# evpr_mini.net
KiCad netlist of a schematic drawn in EAGLE
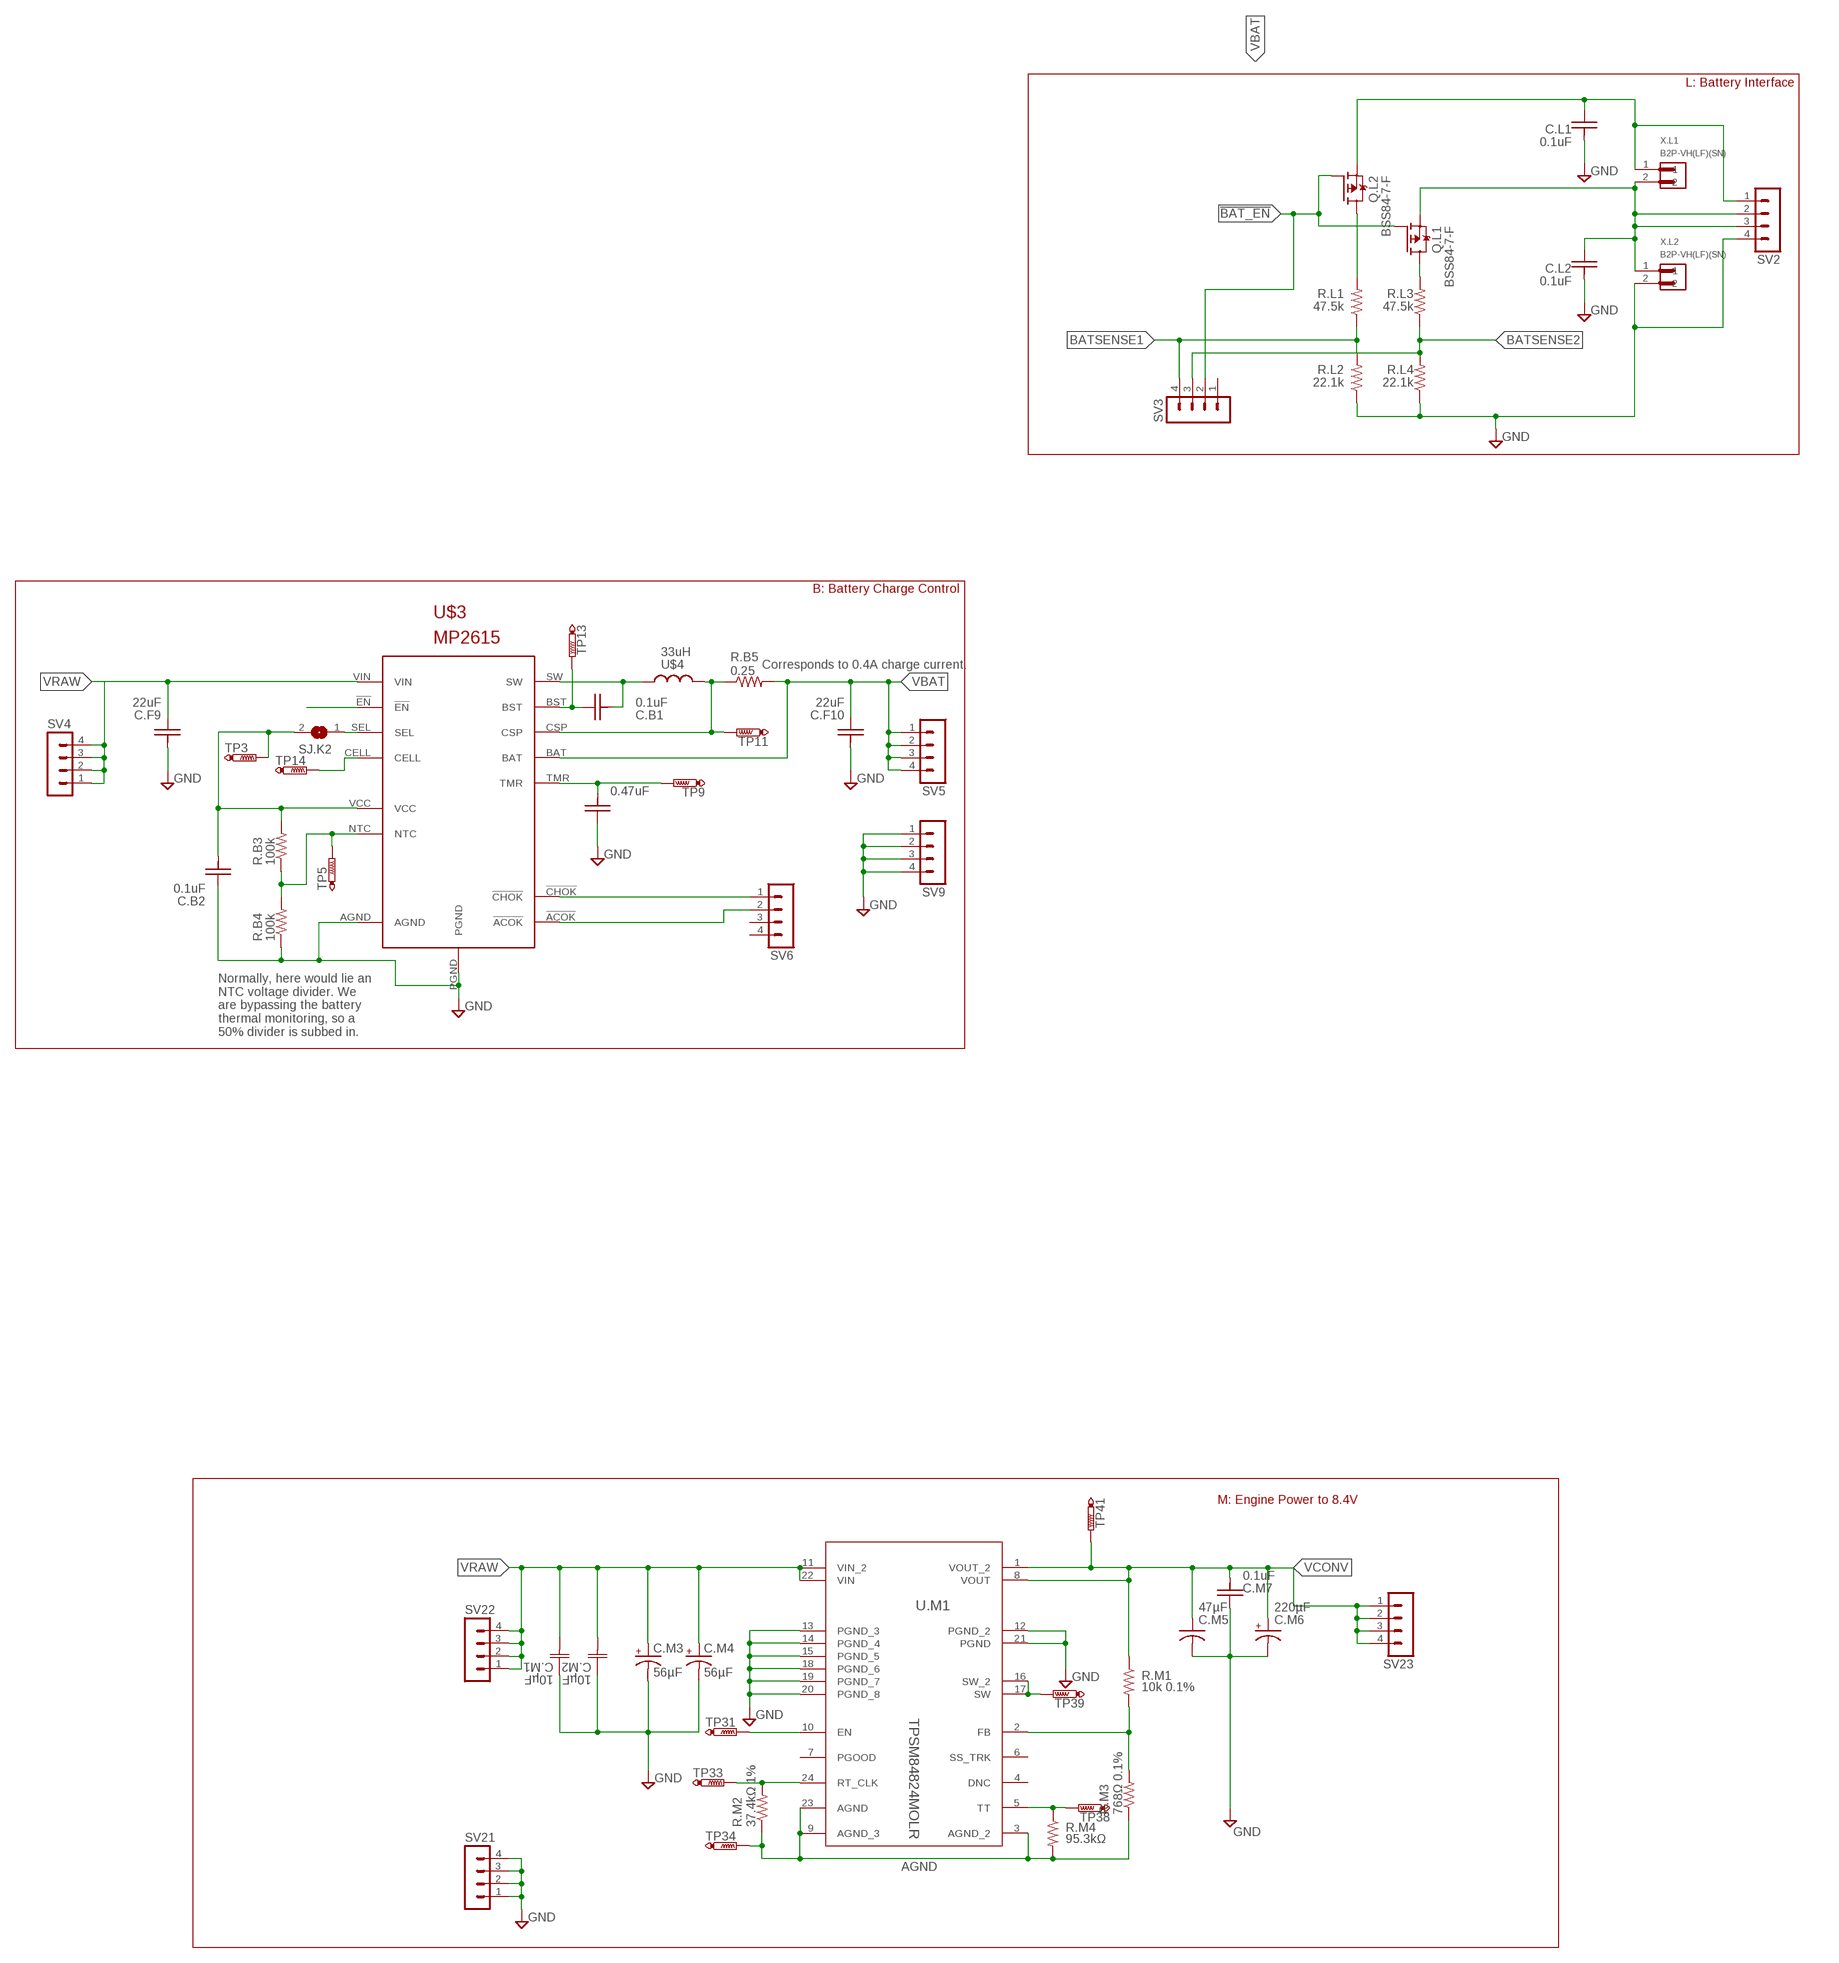
[diagram p0: schematic, sheet 1, part 1 of 2]
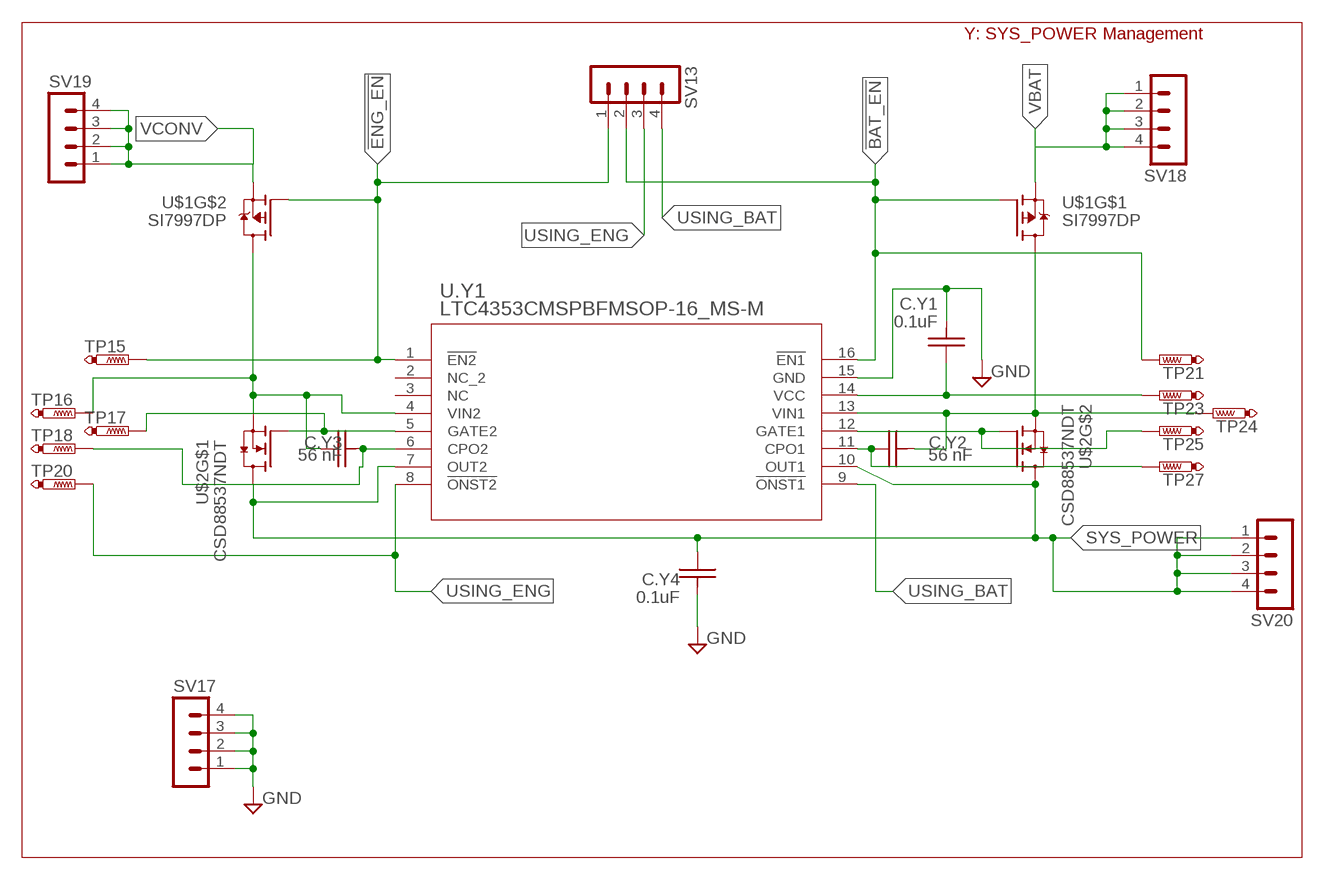
[diagram p1: schematic, sheet 1, part 2 of 2]

(export (version "E")
  (design (tool "Eeschema 10.0.6"))
  (components
    (comp (ref "C.B1")
      (value "0.1uF")
      (footprint "eagle-import:C0603")
      (libsource (lib "eagle-import") (part "C0603"))
    )
    (comp (ref "C.B2")
      (value "0.1uF")
      (footprint "eagle-import:C0603")
      (libsource (lib "eagle-import") (part "C0603"))
    )
    (comp (ref "C.F9")
      (value "22uF")
      (footprint "eagle-import:C0603")
      (libsource (lib "eagle-import") (part "C0603"))
    )
    (comp (ref "C.F10")
      (value "22uF")
      (footprint "eagle-import:C0603")
      (libsource (lib "eagle-import") (part "C0603"))
    )
    (comp (ref "C.J3")
      (value "0.47uF")
      (footprint "eagle-import:C0603")
      (libsource (lib "eagle-import") (part "C0603"))
    )
    (comp (ref "C.L1")
      (value "0.1uF")
      (footprint "eagle-import:C0603")
      (libsource (lib "eagle-import") (part "C0603"))
    )
    (comp (ref "C.L2")
      (value "0.1uF")
      (footprint "eagle-import:C0603")
      (libsource (lib "eagle-import") (part "C0603"))
    )
    (comp (ref "C.M1")
      (value "10µF")
      (footprint "eagle-import:CAP_3225")
      (libsource (lib "eagle-import") (part "C3225X7R1E106K250AC"))
    )
    (comp (ref "C.M2")
      (value "10µF")
      (footprint "eagle-import:CAP_3225")
      (libsource (lib "eagle-import") (part "C3225X7R1E106K250AC"))
    )
    (comp (ref "C.M3")
      (value "56µF")
      (footprint "eagle-import:OSCON_SVPF_6.3MM")
      (libsource (lib "eagle-import") (part "6.3MMCAP"))
    )
    (comp (ref "C.M4")
      (value "56µF")
      (footprint "eagle-import:OSCON_SVPF_6.3MM")
      (libsource (lib "eagle-import") (part "6.3MMCAP"))
    )
    (comp (ref "C.M5")
      (value "47µF")
      (footprint "eagle-import:C1210")
      (libsource (lib "eagle-import") (part "C-USC1210"))
    )
    (comp (ref "C.M6")
      (value "220µF")
      (footprint "eagle-import:C6CYLCAP")
      (libsource (lib "eagle-import") (part "WURTH875115352003"))
    )
    (comp (ref "C.M7")
      (value "0.1uF")
      (footprint "eagle-import:C0603")
      (libsource (lib "eagle-import") (part "C0603"))
    )
    (comp (ref "C.Y1")
      (value "0.1uF")
      (footprint "eagle-import:C0603")
      (libsource (lib "eagle-import") (part "C0603"))
    )
    (comp (ref "C.Y2")
      (value "56 nF")
      (footprint "eagle-import:C0603")
      (libsource (lib "eagle-import") (part "C0603"))
    )
    (comp (ref "C.Y3")
      (value "56 nF")
      (footprint "eagle-import:C0603")
      (libsource (lib "eagle-import") (part "C0603"))
    )
    (comp (ref "C.Y4")
      (value "0.1uF")
      (footprint "eagle-import:C0603")
      (libsource (lib "eagle-import") (part "C0603"))
    )
    (comp (ref "Q.L1")
      (value "BSS84-7-F")
      (footprint "eagle-import:SOT23")
      (libsource (lib "eagle-import") (part "BSS84-7-F"))
    )
    (comp (ref "Q.L2")
      (value "BSS84-7-F")
      (footprint "eagle-import:SOT23")
      (libsource (lib "eagle-import") (part "BSS84-7-F"))
    )
    (comp (ref "R.B3")
      (value "100k")
      (footprint "eagle-import:R0603")
      (libsource (lib "eagle-import") (part "R0603"))
    )
    (comp (ref "R.B4")
      (value "100k")
      (footprint "eagle-import:R0603")
      (libsource (lib "eagle-import") (part "R0603"))
    )
    (comp (ref "R.B5")
      (value "0.25")
      (footprint "eagle-import:R0603")
      (libsource (lib "eagle-import") (part "R0603"))
    )
    (comp (ref "R.L1")
      (value "47.5k")
      (footprint "eagle-import:R0603")
      (libsource (lib "eagle-import") (part "R0603"))
    )
    (comp (ref "R.L2")
      (value "22.1k")
      (footprint "eagle-import:R0603")
      (libsource (lib "eagle-import") (part "R0603"))
    )
    (comp (ref "R.L3")
      (value "47.5k")
      (footprint "eagle-import:R0603")
      (libsource (lib "eagle-import") (part "R0603"))
    )
    (comp (ref "R.L4")
      (value "22.1k")
      (footprint "eagle-import:R0603")
      (libsource (lib "eagle-import") (part "R0603"))
    )
    (comp (ref "R.M1")
      (value "10k 0.1%")
      (footprint "eagle-import:R0603")
      (libsource (lib "eagle-import") (part "R0603"))
    )
    (comp (ref "R.M2")
      (value "37.4kΩ 1%")
      (footprint "eagle-import:R0603")
      (libsource (lib "eagle-import") (part "R0603"))
    )
    (comp (ref "R.M3")
      (value "768Ω 0.1%")
      (footprint "eagle-import:R0603")
      (libsource (lib "eagle-import") (part "R0603"))
    )
    (comp (ref "R.M4")
      (value "95.3kΩ")
      (footprint "eagle-import:R0603")
      (libsource (lib "eagle-import") (part "R0603"))
    )
    (comp (ref "SJ.K2")
      (value "SJ")
      (footprint "eagle-import:SJ")
      (libsource (lib "eagle-import") (part "SJ"))
    )
    (comp (ref "SV2")
      (value "MA04-1")
      (footprint "eagle-import:MA04-1")
      (libsource (lib "eagle-import") (part "MA04-1"))
    )
    (comp (ref "SV3")
      (value "MA04-1")
      (footprint "eagle-import:MA04-1")
      (libsource (lib "eagle-import") (part "MA04-1"))
    )
    (comp (ref "SV4")
      (value "MA04-1")
      (footprint "eagle-import:MA04-1")
      (libsource (lib "eagle-import") (part "MA04-1"))
    )
    (comp (ref "SV5")
      (value "MA04-1")
      (footprint "eagle-import:MA04-1")
      (libsource (lib "eagle-import") (part "MA04-1"))
    )
    (comp (ref "SV6")
      (value "MA04-1")
      (footprint "eagle-import:MA04-1")
      (libsource (lib "eagle-import") (part "MA04-1"))
    )
    (comp (ref "SV9")
      (value "MA04-1")
      (footprint "eagle-import:MA04-1")
      (libsource (lib "eagle-import") (part "MA04-1"))
    )
    (comp (ref "SV13")
      (value "MA04-1")
      (footprint "eagle-import:MA04-1")
      (libsource (lib "eagle-import") (part "MA04-1"))
    )
    (comp (ref "SV17")
      (value "MA04-1")
      (footprint "eagle-import:MA04-1")
      (libsource (lib "eagle-import") (part "MA04-1"))
    )
    (comp (ref "SV18")
      (value "MA04-1")
      (footprint "eagle-import:MA04-1")
      (libsource (lib "eagle-import") (part "MA04-1"))
    )
    (comp (ref "SV19")
      (value "MA04-1")
      (footprint "eagle-import:MA04-1")
      (libsource (lib "eagle-import") (part "MA04-1"))
    )
    (comp (ref "SV20")
      (value "MA04-1")
      (footprint "eagle-import:MA04-1")
      (libsource (lib "eagle-import") (part "MA04-1"))
    )
    (comp (ref "SV21")
      (value "MA04-1")
      (footprint "eagle-import:MA04-1")
      (libsource (lib "eagle-import") (part "MA04-1"))
    )
    (comp (ref "SV22")
      (value "MA04-1")
      (footprint "eagle-import:MA04-1")
      (libsource (lib "eagle-import") (part "MA04-1"))
    )
    (comp (ref "SV23")
      (value "MA04-1")
      (footprint "eagle-import:MA04-1")
      (libsource (lib "eagle-import") (part "MA04-1"))
    )
    (comp (ref "TP3")
      (value "PTR1TP10R")
      (footprint "eagle-import:TP10R")
      (libsource (lib "eagle-import") (part "PTR1TP10R"))
    )
    (comp (ref "TP5")
      (value "PTR1TP10R")
      (footprint "eagle-import:TP10R")
      (libsource (lib "eagle-import") (part "PTR1TP10R"))
    )
    (comp (ref "TP9")
      (value "PTR1TP10R")
      (footprint "eagle-import:TP10R")
      (libsource (lib "eagle-import") (part "PTR1TP10R"))
    )
    (comp (ref "TP11")
      (value "PTR1TP10R")
      (footprint "eagle-import:TP10R")
      (libsource (lib "eagle-import") (part "PTR1TP10R"))
    )
    (comp (ref "TP13")
      (value "PTR1TP10R")
      (footprint "eagle-import:TP10R")
      (libsource (lib "eagle-import") (part "PTR1TP10R"))
    )
    (comp (ref "TP14")
      (value "PTR1TP10R")
      (footprint "eagle-import:TP10R")
      (libsource (lib "eagle-import") (part "PTR1TP10R"))
    )
    (comp (ref "TP15")
      (value "PTR1TP10R")
      (footprint "eagle-import:TP10R")
      (libsource (lib "eagle-import") (part "PTR1TP10R"))
    )
    (comp (ref "TP16")
      (value "PTR1TP10R")
      (footprint "eagle-import:TP10R")
      (libsource (lib "eagle-import") (part "PTR1TP10R"))
    )
    (comp (ref "TP17")
      (value "PTR1TP10R")
      (footprint "eagle-import:TP10R")
      (libsource (lib "eagle-import") (part "PTR1TP10R"))
    )
    (comp (ref "TP18")
      (value "PTR1TP10R")
      (footprint "eagle-import:TP10R")
      (libsource (lib "eagle-import") (part "PTR1TP10R"))
    )
    (comp (ref "TP20")
      (value "PTR1TP10R")
      (footprint "eagle-import:TP10R")
      (libsource (lib "eagle-import") (part "PTR1TP10R"))
    )
    (comp (ref "TP21")
      (value "PTR1TP10R")
      (footprint "eagle-import:TP10R")
      (libsource (lib "eagle-import") (part "PTR1TP10R"))
    )
    (comp (ref "TP23")
      (value "PTR1TP10R")
      (footprint "eagle-import:TP10R")
      (libsource (lib "eagle-import") (part "PTR1TP10R"))
    )
    (comp (ref "TP24")
      (value "PTR1TP10R")
      (footprint "eagle-import:TP10R")
      (libsource (lib "eagle-import") (part "PTR1TP10R"))
    )
    (comp (ref "TP25")
      (value "PTR1TP10R")
      (footprint "eagle-import:TP10R")
      (libsource (lib "eagle-import") (part "PTR1TP10R"))
    )
    (comp (ref "TP27")
      (value "PTR1TP10R")
      (footprint "eagle-import:TP10R")
      (libsource (lib "eagle-import") (part "PTR1TP10R"))
    )
    (comp (ref "TP31")
      (value "PTR1TP10R")
      (footprint "eagle-import:TP10R")
      (libsource (lib "eagle-import") (part "PTR1TP10R"))
    )
    (comp (ref "TP33")
      (value "PTR1TP10R")
      (footprint "eagle-import:TP10R")
      (libsource (lib "eagle-import") (part "PTR1TP10R"))
    )
    (comp (ref "TP34")
      (value "PTR1TP10R")
      (footprint "eagle-import:TP10R")
      (libsource (lib "eagle-import") (part "PTR1TP10R"))
    )
    (comp (ref "TP38")
      (value "PTR1TP10R")
      (footprint "eagle-import:TP10R")
      (libsource (lib "eagle-import") (part "PTR1TP10R"))
    )
    (comp (ref "TP39")
      (value "PTR1TP10R")
      (footprint "eagle-import:TP10R")
      (libsource (lib "eagle-import") (part "PTR1TP10R"))
    )
    (comp (ref "TP41")
      (value "PTR1TP10R")
      (footprint "eagle-import:TP10R")
      (libsource (lib "eagle-import") (part "PTR1TP10R"))
    )
    (comp (ref "U$1")
      (value "SI7997DP")
      (footprint "eagle-import:POWERPAK_SO8DUAL")
      (libsource (lib "eagle-import") (part "SI7997DP"))
    )
    (comp (ref "U$2")
      (value "CSD88537NDT")
      (footprint "eagle-import:SOIC8")
      (libsource (lib "eagle-import") (part "CSD88537NDT"))
    )
    (comp (ref "U$3")
      (value "MP2615")
      (footprint "eagle-import:QFN16")
      (libsource (lib "eagle-import") (part "MP2615"))
    )
    (comp (ref "U$4")
      (value "33uH")
      (footprint "eagle-import:SRN5040TA")
      (libsource (lib "eagle-import") (part "SRN5040TA-330M"))
    )
    (comp (ref "U.M1")
      (value "TPSM84824MOLR")
      (footprint "eagle-import:MOL0024A")
      (libsource (lib "eagle-import") (part "TPSM84824MOLR"))
    )
    (comp (ref "U.Y1")
      (value "LTC4353CMSPBFMSOP-16_MS-M")
      (footprint "eagle-import:MSOP-16_MS-M")
      (fields (field (name "MANUFACTURER_PART_NUMBER") "LTC4353CMS#PBF"))
      (libsource (lib "eagle-import") (part "LTC4353CMSPBFMSOP-16_MS-M"))
    )
    (comp (ref "X.L1")
      (value "B2P-VH(LF)(SN)")
      (footprint "eagle-import:JST_B2P-VH(LF)(SN)")
      (fields (field (name "MF") "JST Sales") (field (name "MP") "B2P-VH_LF__SN_"))
      (libsource (lib "eagle-import") (part "B2P-VH(LF)(SN)"))
    )
    (comp (ref "X.L2")
      (value "B2P-VH(LF)(SN)")
      (footprint "eagle-import:JST_B2P-VH(LF)(SN)")
      (fields (field (name "MF") "JST Sales") (field (name "MP") "B2P-VH_LF__SN_"))
      (libsource (lib "eagle-import") (part "B2P-VH(LF)(SN)"))
    )
  )
  (nets
    (net (code "1") (name "/AGND") (class "Default")
      (node (ref "R.M2") (pin "1") (pinfunction "1_1") (pintype "passive"))
      (node (ref "R.M3") (pin "1") (pinfunction "1_1") (pintype "passive"))
      (node (ref "R.M4") (pin "2") (pinfunction "2_2") (pintype "passive"))
      (node (ref "TP34") (pin "TP") (pinfunction "TP_TP") (pintype "input"))
      (node (ref "U.M1") (pin "23") (pinfunction "AGND_23") (pintype "power_in"))
      (node (ref "U.M1") (pin "3") (pinfunction "AGND_2_3") (pintype "power_in"))
      (node (ref "U.M1") (pin "9") (pinfunction "AGND_3_9") (pintype "power_in"))
    )
    (net (code "2") (name "/~{BAT_EN}") (class "Default")
      (node (ref "Q.L1") (pin "1") (pinfunction "G_1") (pintype "passive"))
      (node (ref "Q.L2") (pin "1") (pinfunction "G_1") (pintype "passive"))
      (node (ref "SV13") (pin "2") (pinfunction "2_2") (pintype "passive"))
      (node (ref "SV3") (pin "2") (pinfunction "2_2") (pintype "passive"))
      (node (ref "TP21") (pin "TP") (pinfunction "TP_TP") (pintype "input"))
      (node (ref "U$1") (pin "P$2") (pinfunction "G_P$2") (pintype "passive"))
      (node (ref "U.Y1") (pin "16") (pinfunction "~{EN1}_16") (pintype "input"))
    )
    (net (code "3") (name "/~{ENG_EN}") (class "Default")
      (node (ref "SV13") (pin "1") (pinfunction "1_1") (pintype "passive"))
      (node (ref "TP15") (pin "TP") (pinfunction "TP_TP") (pintype "input"))
      (node (ref "U$1") (pin "P$4") (pinfunction "G_P$4") (pintype "passive"))
      (node (ref "U.Y1") (pin "1") (pinfunction "~{EN2}_1") (pintype "input"))
    )
    (net (code "4") (name "BATSENSE1") (class "Default")
      (node (ref "R.L1") (pin "1") (pinfunction "1_1") (pintype "passive"))
      (node (ref "R.L2") (pin "2") (pinfunction "2_2") (pintype "passive"))
      (node (ref "SV3") (pin "4") (pinfunction "4_4") (pintype "passive"))
    )
    (net (code "5") (name "BATSENSE2") (class "Default")
      (node (ref "R.L3") (pin "1") (pinfunction "1_1") (pintype "passive"))
      (node (ref "R.L4") (pin "2") (pinfunction "2_2") (pintype "passive"))
      (node (ref "SV3") (pin "3") (pinfunction "3_3") (pintype "passive"))
    )
    (net (code "6") (name "GND") (class "Default")
      (node (ref "C.B2") (pin "1") (pinfunction "1_1") (pintype "passive"))
      (node (ref "C.F10") (pin "2") (pinfunction "2_2") (pintype "passive"))
      (node (ref "C.F9") (pin "2") (pinfunction "2_2") (pintype "passive"))
      (node (ref "C.J3") (pin "1") (pinfunction "1_1") (pintype "passive"))
      (node (ref "C.L1") (pin "2") (pinfunction "2_2") (pintype "passive"))
      (node (ref "C.L2") (pin "2") (pinfunction "2_2") (pintype "passive"))
      (node (ref "C.M1") (pin "1") (pinfunction "1_1") (pintype "passive"))
      (node (ref "C.M2") (pin "1") (pinfunction "1_1") (pintype "passive"))
      (node (ref "C.M3") (pin "-") (pinfunction "-_-") (pintype "passive"))
      (node (ref "C.M4") (pin "-") (pinfunction "-_-") (pintype "passive"))
      (node (ref "C.M5") (pin "2") (pinfunction "2_2") (pintype "passive"))
      (node (ref "C.M6") (pin "P$1") (pinfunction "-_P$1") (pintype "passive"))
      (node (ref "C.M7") (pin "1") (pinfunction "1_1") (pintype "passive"))
      (node (ref "C.Y1") (pin "2") (pinfunction "2_2") (pintype "passive"))
      (node (ref "C.Y4") (pin "2") (pinfunction "2_2") (pintype "passive"))
      (node (ref "R.B4") (pin "1") (pinfunction "1_1") (pintype "passive"))
      (node (ref "R.L2") (pin "1") (pinfunction "1_1") (pintype "passive"))
      (node (ref "R.L4") (pin "1") (pinfunction "1_1") (pintype "passive"))
      (node (ref "SV17") (pin "1") (pinfunction "1_1") (pintype "passive"))
      (node (ref "SV17") (pin "2") (pinfunction "2_2") (pintype "passive"))
      (node (ref "SV17") (pin "3") (pinfunction "3_3") (pintype "passive"))
      (node (ref "SV17") (pin "4") (pinfunction "4_4") (pintype "passive"))
      (node (ref "SV2") (pin "4") (pinfunction "4_4") (pintype "passive"))
      (node (ref "SV21") (pin "1") (pinfunction "1_1") (pintype "passive"))
      (node (ref "SV21") (pin "2") (pinfunction "2_2") (pintype "passive"))
      (node (ref "SV21") (pin "3") (pinfunction "3_3") (pintype "passive"))
      (node (ref "SV21") (pin "4") (pinfunction "4_4") (pintype "passive"))
      (node (ref "SV9") (pin "1") (pinfunction "1_1") (pintype "passive"))
      (node (ref "SV9") (pin "2") (pinfunction "2_2") (pintype "passive"))
      (node (ref "SV9") (pin "3") (pinfunction "3_3") (pintype "passive"))
      (node (ref "SV9") (pin "4") (pinfunction "4_4") (pintype "passive"))
      (node (ref "U$3") (pin "AGND") (pinfunction "AGND_AGND") (pintype "bidirectional"))
      (node (ref "U$3") (pin "PGND") (pinfunction "PGND_PGND") (pintype "bidirectional"))
      (node (ref "U.M1") (pin "12") (pinfunction "PGND_2_12") (pintype "power_in"))
      (node (ref "U.M1") (pin "13") (pinfunction "PGND_3_13") (pintype "power_in"))
      (node (ref "U.M1") (pin "14") (pinfunction "PGND_4_14") (pintype "power_in"))
      (node (ref "U.M1") (pin "15") (pinfunction "PGND_5_15") (pintype "power_in"))
      (node (ref "U.M1") (pin "18") (pinfunction "PGND_6_18") (pintype "power_in"))
      (node (ref "U.M1") (pin "19") (pinfunction "PGND_7_19") (pintype "power_in"))
      (node (ref "U.M1") (pin "20") (pinfunction "PGND_8_20") (pintype "power_in"))
      (node (ref "U.M1") (pin "21") (pinfunction "PGND_21") (pintype "power_in"))
      (node (ref "U.Y1") (pin "15") (pinfunction "GND_15") (pintype "power_in"))
      (node (ref "X.L2") (pin "2") (pinfunction "2_2") (pintype "passive"))
    )
    (net (code "7") (name "Net-(C.B1-Pad1)") (class "Default")
      (node (ref "C.B1") (pin "1") (pinfunction "1_1") (pintype "passive"))
      (node (ref "TP13") (pin "TP") (pinfunction "TP_TP") (pintype "input"))
      (node (ref "U$3") (pin "BST") (pinfunction "BST_BST") (pintype "bidirectional"))
    )
    (net (code "8") (name "Net-(C.B2-Pad2)") (class "Default")
      (node (ref "C.B2") (pin "2") (pinfunction "2_2") (pintype "passive"))
      (node (ref "R.B3") (pin "2") (pinfunction "2_2") (pintype "passive"))
      (node (ref "SJ.K2") (pin "2") (pinfunction "2_2") (pintype "passive"))
      (node (ref "TP3") (pin "TP") (pinfunction "TP_TP") (pintype "input"))
      (node (ref "U$3") (pin "VCC") (pinfunction "VCC_VCC") (pintype "bidirectional"))
    )
    (net (code "9") (name "Net-(C.J3-Pad2)") (class "Default")
      (node (ref "C.J3") (pin "2") (pinfunction "2_2") (pintype "passive"))
      (node (ref "TP9") (pin "TP") (pinfunction "TP_TP") (pintype "input"))
      (node (ref "U$3") (pin "TMR") (pinfunction "TMR_TMR") (pintype "bidirectional"))
    )
    (net (code "10") (name "Net-(Q.L1-D)") (class "Default")
      (node (ref "Q.L1") (pin "3") (pinfunction "D_3") (pintype "passive"))
      (node (ref "R.L3") (pin "2") (pinfunction "2_2") (pintype "passive"))
    )
    (net (code "11") (name "Net-(Q.L1-S)") (class "Default")
      (node (ref "C.L2") (pin "1") (pinfunction "1_1") (pintype "passive"))
      (node (ref "Q.L1") (pin "2") (pinfunction "S_2") (pintype "passive"))
      (node (ref "SV2") (pin "2") (pinfunction "2_2") (pintype "passive"))
      (node (ref "SV2") (pin "3") (pinfunction "3_3") (pintype "passive"))
      (node (ref "X.L1") (pin "2") (pinfunction "2_2") (pintype "passive"))
      (node (ref "X.L2") (pin "1") (pinfunction "1_1") (pintype "passive"))
    )
    (net (code "12") (name "Net-(Q.L2-D)") (class "Default")
      (node (ref "Q.L2") (pin "3") (pinfunction "D_3") (pintype "passive"))
      (node (ref "R.L1") (pin "2") (pinfunction "2_2") (pintype "passive"))
    )
    (net (code "13") (name "Net-(R.B3-Pad1)") (class "Default")
      (node (ref "R.B3") (pin "1") (pinfunction "1_1") (pintype "passive"))
      (node (ref "R.B4") (pin "2") (pinfunction "2_2") (pintype "passive"))
      (node (ref "TP5") (pin "TP") (pinfunction "TP_TP") (pintype "input"))
      (node (ref "U$3") (pin "NTC") (pinfunction "NTC_NTC") (pintype "bidirectional"))
    )
    (net (code "14") (name "Net-(SJ.K2-Pad1)") (class "Default")
      (node (ref "SJ.K2") (pin "1") (pinfunction "1_1") (pintype "passive"))
      (node (ref "U$3") (pin "SEL") (pinfunction "SEL_SEL") (pintype "bidirectional"))
    )
    (net (code "15") (name "Net-(TP14-PadTP)") (class "Default")
      (node (ref "TP14") (pin "TP") (pinfunction "TP_TP") (pintype "input"))
      (node (ref "U$3") (pin "CELL") (pinfunction "CELL_CELL") (pintype "bidirectional"))
    )
    (net (code "16") (name "Net-(U$1A-D)") (class "Default")
      (node (ref "C.Y2") (pin "2") (pinfunction "2_2") (pintype "passive"))
      (node (ref "TP24") (pin "TP") (pinfunction "TP_TP") (pintype "input"))
      (node (ref "U$1") (pin "D$1B") (pinfunction "D_D$1B") (pintype "passive"))
      (node (ref "U$2") (pin "3") (pinfunction "S_3") (pintype "passive"))
      (node (ref "U.Y1") (pin "13") (pinfunction "VIN1_13") (pintype "input"))
    )
    (net (code "17") (name "Net-(U$1B-D)") (class "Default")
      (node (ref "C.Y3") (pin "1") (pinfunction "1_1") (pintype "passive"))
      (node (ref "TP16") (pin "TP") (pinfunction "TP_TP") (pintype "input"))
      (node (ref "U$1") (pin "D$2A") (pinfunction "D_D$2A") (pintype "passive"))
      (node (ref "U$2") (pin "1") (pinfunction "S_1") (pintype "passive"))
      (node (ref "U.Y1") (pin "4") (pinfunction "VIN2_4") (pintype "input"))
    )
    (net (code "18") (name "Net-(U$2A-G)") (class "Default")
      (node (ref "TP17") (pin "TP") (pinfunction "TP_TP") (pintype "input"))
      (node (ref "U$2") (pin "2") (pinfunction "G_2") (pintype "passive"))
      (node (ref "U.Y1") (pin "5") (pinfunction "GATE2_5") (pintype "output"))
    )
    (net (code "19") (name "Net-(U$2B-G)") (class "Default")
      (node (ref "TP25") (pin "TP") (pinfunction "TP_TP") (pintype "input"))
      (node (ref "U$2") (pin "4") (pinfunction "G_4") (pintype "passive"))
      (node (ref "U.Y1") (pin "12") (pinfunction "GATE1_12") (pintype "output"))
    )
    (net (code "20") (name "Net-(U$3-~{ACOK})") (class "Default")
      (node (ref "SV6") (pin "2") (pinfunction "2_2") (pintype "passive"))
      (node (ref "U$3") (pin "!ACOK") (pinfunction "~{ACOK}_!ACOK") (pintype "bidirectional"))
    )
    (net (code "21") (name "Net-(U$3-~{CHOK})") (class "Default")
      (node (ref "SV6") (pin "1") (pinfunction "1_1") (pintype "passive"))
      (node (ref "U$3") (pin "!CHOK") (pinfunction "~{CHOK}_!CHOK") (pintype "bidirectional"))
    )
    (net (code "22") (name "Net-(U$4-1)") (class "Default")
      (node (ref "C.B1") (pin "2") (pinfunction "2_2") (pintype "passive"))
      (node (ref "U$3") (pin "SW") (pinfunction "SW_SW") (pintype "bidirectional"))
      (node (ref "U$4") (pin "P$1") (pinfunction "1_P$1") (pintype "passive"))
    )
    (net (code "23") (name "Net-(U$4-2)") (class "Default")
      (node (ref "R.B5") (pin "1") (pinfunction "1_1") (pintype "passive"))
      (node (ref "TP11") (pin "TP") (pinfunction "TP_TP") (pintype "input"))
      (node (ref "U$3") (pin "CSP") (pinfunction "CSP_CSP") (pintype "bidirectional"))
      (node (ref "U$4") (pin "P$2") (pinfunction "2_P$2") (pintype "passive"))
    )
    (net (code "24") (name "Net-(U.M1-EN)") (class "Default")
      (node (ref "TP31") (pin "TP") (pinfunction "TP_TP") (pintype "input"))
      (node (ref "U.M1") (pin "10") (pinfunction "EN_10") (pintype "input"))
    )
    (net (code "25") (name "Net-(U.M1-FB)") (class "Default")
      (node (ref "R.M1") (pin "2") (pinfunction "2_2") (pintype "passive"))
      (node (ref "R.M3") (pin "2") (pinfunction "2_2") (pintype "passive"))
      (node (ref "U.M1") (pin "2") (pinfunction "FB_2") (pintype "input"))
    )
    (net (code "26") (name "Net-(U.M1-RT_CLK)") (class "Default")
      (node (ref "R.M2") (pin "2") (pinfunction "2_2") (pintype "passive"))
      (node (ref "TP33") (pin "TP") (pinfunction "TP_TP") (pintype "input"))
      (node (ref "U.M1") (pin "24") (pinfunction "RT_CLK_24") (pintype "input"))
    )
    (net (code "27") (name "Net-(U.M1-SW)") (class "Default")
      (node (ref "TP39") (pin "TP") (pinfunction "TP_TP") (pintype "input"))
      (node (ref "U.M1") (pin "16") (pinfunction "SW_2_16") (pintype "output"))
      (node (ref "U.M1") (pin "17") (pinfunction "SW_17") (pintype "output"))
    )
    (net (code "28") (name "Net-(U.M1-TT)") (class "Default")
      (node (ref "R.M4") (pin "1") (pinfunction "1_1") (pintype "passive"))
      (node (ref "TP38") (pin "TP") (pinfunction "TP_TP") (pintype "input"))
      (node (ref "U.M1") (pin "5") (pinfunction "TT_5") (pintype "passive"))
    )
    (net (code "29") (name "Net-(U.Y1-CPO1)") (class "Default")
      (node (ref "C.Y2") (pin "1") (pinfunction "1_1") (pintype "passive"))
      (node (ref "TP27") (pin "TP") (pinfunction "TP_TP") (pintype "input"))
      (node (ref "U.Y1") (pin "11") (pinfunction "CPO1_11") (pintype "output"))
    )
    (net (code "30") (name "Net-(U.Y1-CPO2)") (class "Default")
      (node (ref "C.Y3") (pin "2") (pinfunction "2_2") (pintype "passive"))
      (node (ref "TP18") (pin "TP") (pinfunction "TP_TP") (pintype "input"))
      (node (ref "U.Y1") (pin "6") (pinfunction "CPO2_6") (pintype "output"))
    )
    (net (code "31") (name "Net-(U.Y1-VCC)") (class "Default")
      (node (ref "C.Y1") (pin "1") (pinfunction "1_1") (pintype "passive"))
      (node (ref "TP23") (pin "TP") (pinfunction "TP_TP") (pintype "input"))
      (node (ref "U.Y1") (pin "14") (pinfunction "VCC_14") (pintype "power_in"))
    )
    (net (code "32") (name "SYS_POWER") (class "Default")
      (node (ref "C.Y4") (pin "1") (pinfunction "1_1") (pintype "passive"))
      (node (ref "SV20") (pin "1") (pinfunction "1_1") (pintype "passive"))
      (node (ref "SV20") (pin "2") (pinfunction "2_2") (pintype "passive"))
      (node (ref "SV20") (pin "3") (pinfunction "3_3") (pintype "passive"))
      (node (ref "SV20") (pin "4") (pinfunction "4_4") (pintype "passive"))
      (node (ref "U$2") (pin "5") (pinfunction "D_5") (pintype "passive"))
      (node (ref "U$2") (pin "6") (pinfunction "D_6") (pintype "passive"))
      (node (ref "U$2") (pin "7") (pinfunction "D_7") (pintype "passive"))
      (node (ref "U$2") (pin "8") (pinfunction "D_8") (pintype "passive"))
      (node (ref "U.Y1") (pin "10") (pinfunction "OUT1_10") (pintype "output"))
      (node (ref "U.Y1") (pin "7") (pinfunction "OUT2_7") (pintype "output"))
    )
    (net (code "33") (name "USING_BAT") (class "Default")
      (node (ref "SV13") (pin "4") (pinfunction "4_4") (pintype "passive"))
      (node (ref "U.Y1") (pin "9") (pinfunction "~{ONST1}_9") (pintype "output"))
    )
    (net (code "34") (name "USING_ENG") (class "Default")
      (node (ref "SV13") (pin "3") (pinfunction "3_3") (pintype "passive"))
      (node (ref "TP20") (pin "TP") (pinfunction "TP_TP") (pintype "input"))
      (node (ref "U.Y1") (pin "8") (pinfunction "~{ONST2}_8") (pintype "output"))
    )
    (net (code "35") (name "VBAT") (class "Default")
      (node (ref "C.F10") (pin "1") (pinfunction "1_1") (pintype "passive"))
      (node (ref "C.L1") (pin "1") (pinfunction "1_1") (pintype "passive"))
      (node (ref "Q.L2") (pin "2") (pinfunction "S_2") (pintype "passive"))
      (node (ref "R.B5") (pin "2") (pinfunction "2_2") (pintype "passive"))
      (node (ref "SV18") (pin "1") (pinfunction "1_1") (pintype "passive"))
      (node (ref "SV18") (pin "2") (pinfunction "2_2") (pintype "passive"))
      (node (ref "SV18") (pin "3") (pinfunction "3_3") (pintype "passive"))
      (node (ref "SV18") (pin "4") (pinfunction "4_4") (pintype "passive"))
      (node (ref "SV2") (pin "1") (pinfunction "1_1") (pintype "passive"))
      (node (ref "SV5") (pin "1") (pinfunction "1_1") (pintype "passive"))
      (node (ref "SV5") (pin "2") (pinfunction "2_2") (pintype "passive"))
      (node (ref "SV5") (pin "3") (pinfunction "3_3") (pintype "passive"))
      (node (ref "SV5") (pin "4") (pinfunction "4_4") (pintype "passive"))
      (node (ref "U$1") (pin "P$1") (pinfunction "S_P$1") (pintype "passive"))
      (node (ref "U$3") (pin "BAT") (pinfunction "BAT_BAT") (pintype "bidirectional"))
      (node (ref "X.L1") (pin "1") (pinfunction "1_1") (pintype "passive"))
    )
    (net (code "36") (name "VCONV") (class "Default")
      (node (ref "C.M5") (pin "1") (pinfunction "1_1") (pintype "passive"))
      (node (ref "C.M6") (pin "P$2") (pinfunction "+_P$2") (pintype "passive"))
      (node (ref "C.M7") (pin "2") (pinfunction "2_2") (pintype "passive"))
      (node (ref "R.M1") (pin "1") (pinfunction "1_1") (pintype "passive"))
      (node (ref "SV19") (pin "1") (pinfunction "1_1") (pintype "passive"))
      (node (ref "SV19") (pin "2") (pinfunction "2_2") (pintype "passive"))
      (node (ref "SV19") (pin "3") (pinfunction "3_3") (pintype "passive"))
      (node (ref "SV19") (pin "4") (pinfunction "4_4") (pintype "passive"))
      (node (ref "SV23") (pin "1") (pinfunction "1_1") (pintype "passive"))
      (node (ref "SV23") (pin "2") (pinfunction "2_2") (pintype "passive"))
      (node (ref "SV23") (pin "3") (pinfunction "3_3") (pintype "passive"))
      (node (ref "SV23") (pin "4") (pinfunction "4_4") (pintype "passive"))
      (node (ref "TP41") (pin "TP") (pinfunction "TP_TP") (pintype "input"))
      (node (ref "U$1") (pin "P$3") (pinfunction "S_P$3") (pintype "passive"))
      (node (ref "U.M1") (pin "1") (pinfunction "VOUT_2_1") (pintype "power_in"))
      (node (ref "U.M1") (pin "8") (pinfunction "VOUT_8") (pintype "power_in"))
    )
    (net (code "37") (name "VRAW") (class "Default")
      (node (ref "C.F9") (pin "1") (pinfunction "1_1") (pintype "passive"))
      (node (ref "C.M1") (pin "2") (pinfunction "2_2") (pintype "passive"))
      (node (ref "C.M2") (pin "2") (pinfunction "2_2") (pintype "passive"))
      (node (ref "C.M3") (pin "+") (pinfunction "+_+") (pintype "passive"))
      (node (ref "C.M4") (pin "+") (pinfunction "+_+") (pintype "passive"))
      (node (ref "SV22") (pin "1") (pinfunction "1_1") (pintype "passive"))
      (node (ref "SV22") (pin "2") (pinfunction "2_2") (pintype "passive"))
      (node (ref "SV22") (pin "3") (pinfunction "3_3") (pintype "passive"))
      (node (ref "SV22") (pin "4") (pinfunction "4_4") (pintype "passive"))
      (node (ref "SV4") (pin "1") (pinfunction "1_1") (pintype "passive"))
      (node (ref "SV4") (pin "2") (pinfunction "2_2") (pintype "passive"))
      (node (ref "SV4") (pin "3") (pinfunction "3_3") (pintype "passive"))
      (node (ref "SV4") (pin "4") (pinfunction "4_4") (pintype "passive"))
      (node (ref "U$3") (pin "VIN") (pinfunction "VIN_VIN") (pintype "bidirectional"))
      (node (ref "U.M1") (pin "11") (pinfunction "VIN_2_11") (pintype "power_in"))
      (node (ref "U.M1") (pin "22") (pinfunction "VIN_22") (pintype "power_in"))
    )
    (net (code "38") (name "unconnected-(SV3-Pad1)") (class "Default")
      (node (ref "SV3") (pin "1") (pinfunction "1_1") (pintype "passive"))
    )
    (net (code "39") (name "unconnected-(SV6-Pad3)") (class "Default")
      (node (ref "SV6") (pin "3") (pinfunction "3_3") (pintype "passive"))
    )
    (net (code "40") (name "unconnected-(SV6-Pad4)") (class "Default")
      (node (ref "SV6") (pin "4") (pinfunction "4_4") (pintype "passive"))
    )
    (net (code "41") (name "unconnected-(U$3-~{EN}-Pad!EN)") (class "Default")
      (node (ref "U$3") (pin "!EN") (pinfunction "~{EN}_!EN") (pintype "bidirectional"))
    )
    (net (code "42") (name "unconnected-(U.M1-DNC-Pad4)") (class "Default")
      (node (ref "U.M1") (pin "4") (pinfunction "DNC_4") (pintype "passive"))
    )
    (net (code "43") (name "unconnected-(U.M1-PGOOD-Pad7)") (class "Default")
      (node (ref "U.M1") (pin "7") (pinfunction "PGOOD_7") (pintype "passive"))
    )
    (net (code "44") (name "unconnected-(U.M1-SS_TRK-Pad6)") (class "Default")
      (node (ref "U.M1") (pin "6") (pinfunction "SS_TRK_6") (pintype "passive"))
    )
    (net (code "45") (name "unconnected-(U.Y1-NC-Pad3)") (class "Default")
      (node (ref "U.Y1") (pin "3") (pinfunction "NC_3") (pintype "no_connect"))
    )
    (net (code "46") (name "unconnected-(U.Y1-NC_2-Pad2)") (class "Default")
      (node (ref "U.Y1") (pin "2") (pinfunction "NC_2_2") (pintype "no_connect"))
    )
  )
)
